# Potential_Divider.net
KiCad netlist of a schematic drawn in EAGLE
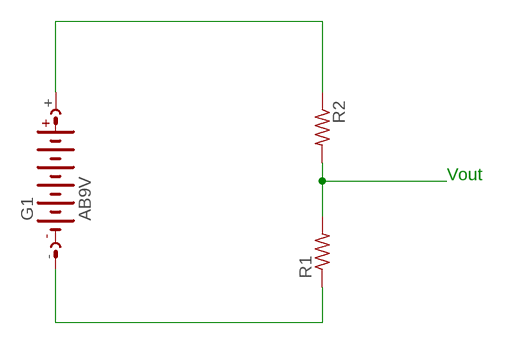
[diagram p0: schematic, sheet 1]

(export (version "E")
  (design (tool "Eeschema 10.0.6"))
  (components
    (comp (ref "G1")
      (value "AB9V")
      (footprint "eagle-import:AB9V")
      (libsource (lib "eagle-import") (part "AB9V"))
    )
    (comp (ref "R1")
      (value "R-US_R0805")
      (footprint "eagle-import:R0805")
      (libsource (lib "eagle-import") (part "R-US_R0805"))
    )
    (comp (ref "R2")
      (value "R-US_R0805")
      (footprint "eagle-import:R0805")
      (libsource (lib "eagle-import") (part "R-US_R0805"))
    )
  )
  (nets
    (net (code "1") (name "Net-(G1-Pad+)") (class "Default")
      (node (ref "G1") (pin "+") (pinfunction "+_+") (pintype "passive"))
      (node (ref "R2") (pin "1") (pinfunction "1_1") (pintype "passive"))
    )
    (net (code "2") (name "Net-(G1-Pad-)") (class "Default")
      (node (ref "G1") (pin "-") (pinfunction "-_-") (pintype "passive"))
      (node (ref "R1") (pin "1") (pinfunction "1_1") (pintype "passive"))
    )
    (net (code "3") (name "Net-(R1-Pad2)") (class "Default")
      (node (ref "R1") (pin "2") (pinfunction "2_2") (pintype "passive"))
      (node (ref "R2") (pin "2") (pinfunction "2_2") (pintype "passive"))
    )
  )
)
